# TCS3200.net
KiCad netlist of a schematic drawn in Altium Designer
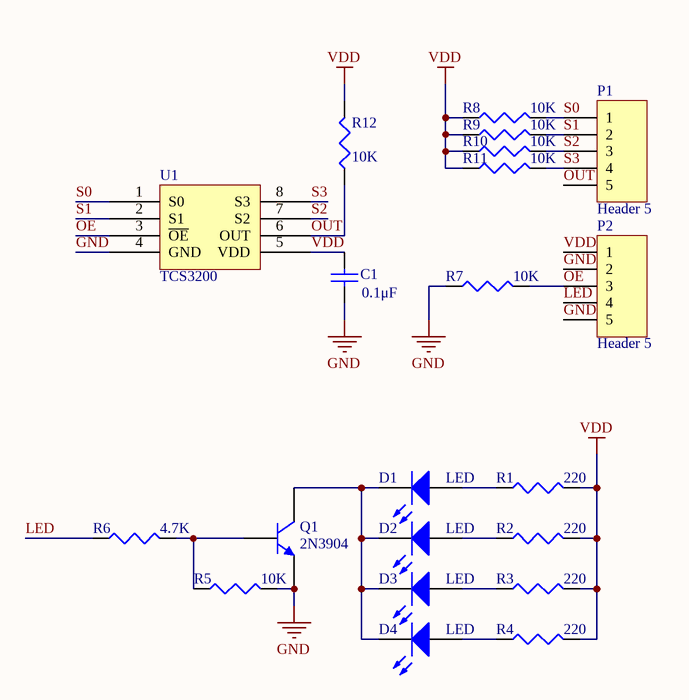
[diagram p0: TCS3200.SchDoc]

(export (version "E")
  (design (tool "Eeschema 10.0.6"))
  (components
    (comp (ref "C1")
      (value "0.1μF")
      (footprint "1608[0603]")
      (description "Capacitor (Semiconductor SIM Model)")
      (fields (field (name "Comment") "Cap Semi") (field (name "PUBLISHER") "Altium Limited"))
      (libsource (lib "Miscellaneous Devices") (part "Cap Semi"))
    )
    (comp (ref "D1")
      (value "LED")
      (footprint "3.2X1.6X1.1")
      (description "Typical RED, GREEN, YELLOW, AMBER GaAs LED")
      (fields (field (name "PUBLISHER") "Altium Limited"))
      (libsource (lib "Miscellaneous Devices") (part "LED2"))
    )
    (comp (ref "D2")
      (value "LED")
      (footprint "3.2X1.6X1.1")
      (description "Typical RED, GREEN, YELLOW, AMBER GaAs LED")
      (fields (field (name "PUBLISHER") "Altium Limited"))
      (libsource (lib "Miscellaneous Devices") (part "LED2"))
    )
    (comp (ref "D3")
      (value "LED")
      (footprint "3.2X1.6X1.1")
      (description "Typical RED, GREEN, YELLOW, AMBER GaAs LED")
      (fields (field (name "PUBLISHER") "Altium Limited"))
      (libsource (lib "Miscellaneous Devices") (part "LED2"))
    )
    (comp (ref "D4")
      (value "LED")
      (footprint "3.2X1.6X1.1")
      (description "Typical RED, GREEN, YELLOW, AMBER GaAs LED")
      (fields (field (name "PUBLISHER") "Altium Limited"))
      (libsource (lib "Miscellaneous Devices") (part "LED2"))
    )
    (comp (ref "P1")
      (value "Header 5")
      (footprint "HDR1X5")
      (description "Header, 5-Pin")
      (fields (field (name "PUBLISHER") "Altium Limited"))
      (libsource (lib "Miscellaneous Connectors") (part "Header 5"))
    )
    (comp (ref "P2")
      (value "Header 5")
      (footprint "HDR1X5")
      (description "Header, 5-Pin")
      (fields (field (name "PUBLISHER") "Altium Limited"))
      (libsource (lib "Miscellaneous Connectors") (part "Header 5"))
    )
    (comp (ref "Q1")
      (value "2N3904")
      (footprint "TO-92A")
      (description "NPN General Purpose Amplifier")
      (fields (field (name "PUBLISHER") "Altium Limited"))
      (libsource (lib "Miscellaneous Devices") (part "2N3904"))
    )
    (comp (ref "R1")
      (value "220")
      (footprint "J1-0603")
      (description "Resistor")
      (fields (field (name "PUBLISHER") "Altium Limited"))
      (libsource (lib "Miscellaneous Devices") (part "Res3"))
    )
    (comp (ref "R2")
      (value "220")
      (footprint "J1-0603")
      (description "Resistor")
      (fields (field (name "PUBLISHER") "Altium Limited"))
      (libsource (lib "Miscellaneous Devices") (part "Res3"))
    )
    (comp (ref "R3")
      (value "220")
      (footprint "J1-0603")
      (description "Resistor")
      (fields (field (name "PUBLISHER") "Altium Limited"))
      (libsource (lib "Miscellaneous Devices") (part "Res3"))
    )
    (comp (ref "R4")
      (value "220")
      (footprint "J1-0603")
      (description "Resistor")
      (fields (field (name "PUBLISHER") "Altium Limited"))
      (libsource (lib "Miscellaneous Devices") (part "Res3"))
    )
    (comp (ref "R5")
      (value "10K")
      (footprint "J1-0603")
      (description "Resistor")
      (fields (field (name "PUBLISHER") "Altium Limited"))
      (libsource (lib "Miscellaneous Devices") (part "Res3"))
    )
    (comp (ref "R6")
      (value "4.7K")
      (footprint "J1-0603")
      (description "Resistor")
      (fields (field (name "PUBLISHER") "Altium Limited"))
      (libsource (lib "Miscellaneous Devices") (part "Res3"))
    )
    (comp (ref "R7")
      (value "10K")
      (footprint "J1-0603")
      (description "Resistor")
      (fields (field (name "PUBLISHER") "Altium Limited"))
      (libsource (lib "Miscellaneous Devices") (part "Res3"))
    )
    (comp (ref "R8")
      (value "10K")
      (footprint "J1-0603")
      (description "Resistor")
      (fields (field (name "PUBLISHER") "Altium Limited"))
      (libsource (lib "Miscellaneous Devices") (part "Res3"))
    )
    (comp (ref "R9")
      (value "10K")
      (footprint "J1-0603")
      (description "Resistor")
      (fields (field (name "PUBLISHER") "Altium Limited"))
      (libsource (lib "Miscellaneous Devices") (part "Res3"))
    )
    (comp (ref "R10")
      (value "10K")
      (footprint "J1-0603")
      (description "Resistor")
      (fields (field (name "PUBLISHER") "Altium Limited"))
      (libsource (lib "Miscellaneous Devices") (part "Res3"))
    )
    (comp (ref "R11")
      (value "10K")
      (footprint "J1-0603")
      (description "Resistor")
      (fields (field (name "PUBLISHER") "Altium Limited"))
      (libsource (lib "Miscellaneous Devices") (part "Res3"))
    )
    (comp (ref "R12")
      (value "10K")
      (footprint "J1-0603")
      (description "Resistor")
      (fields (field (name "PUBLISHER") "Altium Limited"))
      (libsource (lib "Miscellaneous Devices") (part "Res3"))
    )
    (comp (ref "U1") (value "TCS3200") (footprint "TCS3200") (libsource (lib "Sensor") (part "TCS3200")))
  )
  (nets
    (net (code "1") (name "/LED") (class "Default")
      (node (ref "P2") (pin "4") (pinfunction "4_4") (pintype "passive"))
      (node (ref "R6") (pin "1") (pinfunction "1_1") (pintype "passive"))
    )
    (net (code "2") (name "/OE") (class "Default")
      (node (ref "P2") (pin "3") (pinfunction "3_3") (pintype "passive"))
      (node (ref "R7") (pin "2") (pinfunction "2_2") (pintype "passive"))
      (node (ref "U1") (pin "3") (pinfunction "~{OE}_3") (pintype "passive"))
    )
    (net (code "3") (name "/OUT") (class "Default")
      (node (ref "P1") (pin "5") (pinfunction "5_5") (pintype "passive"))
      (node (ref "R12") (pin "1") (pinfunction "1_1") (pintype "passive"))
      (node (ref "U1") (pin "6") (pinfunction "OUT_6") (pintype "passive"))
    )
    (net (code "4") (name "/S0") (class "Default")
      (node (ref "P1") (pin "1") (pinfunction "1_1") (pintype "passive"))
      (node (ref "R8") (pin "2") (pinfunction "2_2") (pintype "passive"))
      (node (ref "U1") (pin "1") (pinfunction "S0_1") (pintype "passive"))
    )
    (net (code "5") (name "/S1") (class "Default")
      (node (ref "P1") (pin "2") (pinfunction "2_2") (pintype "passive"))
      (node (ref "R9") (pin "2") (pinfunction "2_2") (pintype "passive"))
      (node (ref "U1") (pin "2") (pinfunction "S1_2") (pintype "passive"))
    )
    (net (code "6") (name "/S2") (class "Default")
      (node (ref "P1") (pin "3") (pinfunction "3_3") (pintype "passive"))
      (node (ref "R10") (pin "2") (pinfunction "2_2") (pintype "passive"))
      (node (ref "U1") (pin "7") (pinfunction "S2_7") (pintype "passive"))
    )
    (net (code "7") (name "/S3") (class "Default")
      (node (ref "P1") (pin "4") (pinfunction "4_4") (pintype "passive"))
      (node (ref "R11") (pin "2") (pinfunction "2_2") (pintype "passive"))
      (node (ref "U1") (pin "8") (pinfunction "S3_8") (pintype "passive"))
    )
    (net (code "8") (name "GND") (class "Default")
      (node (ref "C1") (pin "1") (pinfunction "1_1") (pintype "passive"))
      (node (ref "P2") (pin "2") (pinfunction "2_2") (pintype "passive"))
      (node (ref "P2") (pin "5") (pinfunction "5_5") (pintype "passive"))
      (node (ref "Q1") (pin "1") (pinfunction "E_1") (pintype "passive"))
      (node (ref "R5") (pin "2") (pinfunction "2_2") (pintype "passive"))
      (node (ref "R7") (pin "1") (pinfunction "1_1") (pintype "passive"))
      (node (ref "U1") (pin "4") (pinfunction "GND_4") (pintype "passive"))
    )
    (net (code "9") (name "Net-(D1-A)") (class "Default")
      (node (ref "D1") (pin "1") (pinfunction "A_1") (pintype "passive"))
      (node (ref "R1") (pin "1") (pinfunction "1_1") (pintype "passive"))
    )
    (net (code "10") (name "Net-(D1-K)") (class "Default")
      (node (ref "D1") (pin "2") (pinfunction "K_2") (pintype "passive"))
      (node (ref "D2") (pin "2") (pinfunction "K_2") (pintype "passive"))
      (node (ref "D3") (pin "2") (pinfunction "K_2") (pintype "passive"))
      (node (ref "D4") (pin "2") (pinfunction "K_2") (pintype "passive"))
      (node (ref "Q1") (pin "3") (pinfunction "C_3") (pintype "passive"))
    )
    (net (code "11") (name "Net-(D2-A)") (class "Default")
      (node (ref "D2") (pin "1") (pinfunction "A_1") (pintype "passive"))
      (node (ref "R2") (pin "1") (pinfunction "1_1") (pintype "passive"))
    )
    (net (code "12") (name "Net-(D3-A)") (class "Default")
      (node (ref "D3") (pin "1") (pinfunction "A_1") (pintype "passive"))
      (node (ref "R3") (pin "1") (pinfunction "1_1") (pintype "passive"))
    )
    (net (code "13") (name "Net-(D4-A)") (class "Default")
      (node (ref "D4") (pin "1") (pinfunction "A_1") (pintype "passive"))
      (node (ref "R4") (pin "1") (pinfunction "1_1") (pintype "passive"))
    )
    (net (code "14") (name "Net-(Q1-B)") (class "Default")
      (node (ref "Q1") (pin "2") (pinfunction "B_2") (pintype "passive"))
      (node (ref "R5") (pin "1") (pinfunction "1_1") (pintype "passive"))
      (node (ref "R6") (pin "2") (pinfunction "2_2") (pintype "passive"))
    )
    (net (code "15") (name "VDD") (class "Default")
      (node (ref "C1") (pin "2") (pinfunction "2_2") (pintype "passive"))
      (node (ref "P2") (pin "1") (pinfunction "1_1") (pintype "passive"))
      (node (ref "R1") (pin "2") (pinfunction "2_2") (pintype "passive"))
      (node (ref "R10") (pin "1") (pinfunction "1_1") (pintype "passive"))
      (node (ref "R11") (pin "1") (pinfunction "1_1") (pintype "passive"))
      (node (ref "R12") (pin "2") (pinfunction "2_2") (pintype "passive"))
      (node (ref "R2") (pin "2") (pinfunction "2_2") (pintype "passive"))
      (node (ref "R3") (pin "2") (pinfunction "2_2") (pintype "passive"))
      (node (ref "R4") (pin "2") (pinfunction "2_2") (pintype "passive"))
      (node (ref "R8") (pin "1") (pinfunction "1_1") (pintype "passive"))
      (node (ref "R9") (pin "1") (pinfunction "1_1") (pintype "passive"))
      (node (ref "U1") (pin "5") (pinfunction "VDD_5") (pintype "passive"))
    )
  )
)
